# Ultrasound_Test_Prototype.net
KiCad netlist of a schematic drawn in Altium Designer
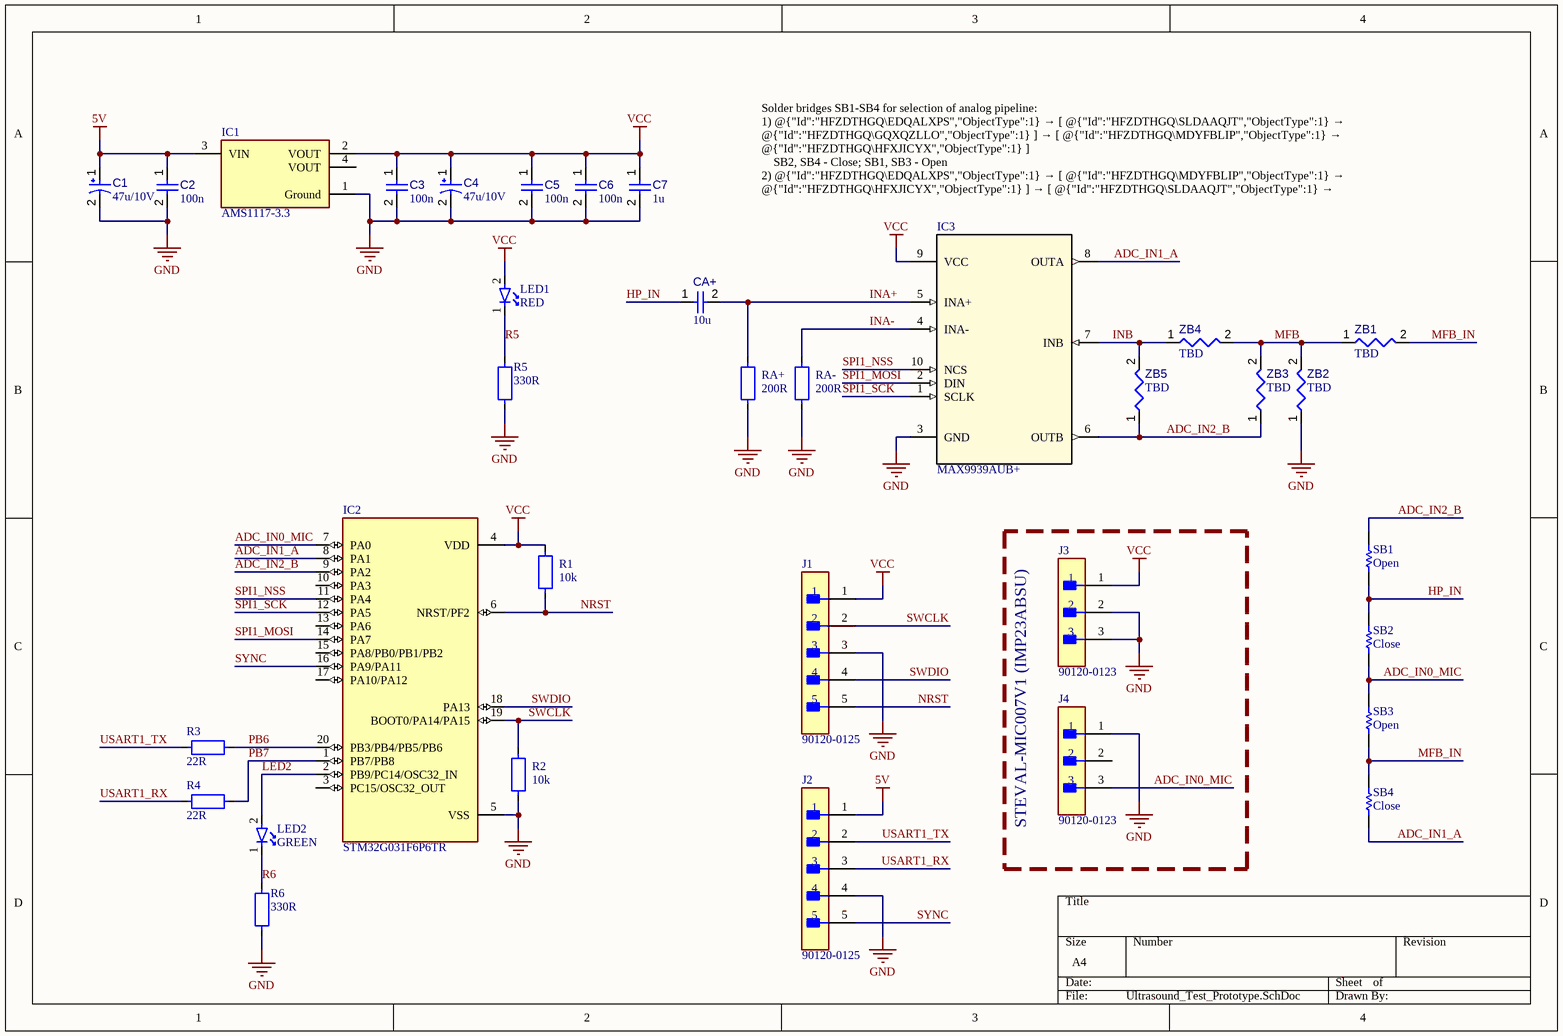
[diagram p0: Ultrasound_Test_Prototype.SchDoc]

(export (version "E")
  (design (tool "Eeschema 10.0.6"))
  (components
    (comp (ref "C1")
      (value "47u/10V")
      (footprint "AVX-TAJ-C-2_L")
      (description "Standard Tantalum, 100 uF, +/- 10%, 10 V, -55 to 125 degC, 2312 (6032 Metric), RoHS, Tape and Reel")
      (fields (field (name "TOLERANCE") "10%") (field (name "MANUFACTURER") "AVX"))
      (libsource (lib "My workspace") (part "CAP-P-2"))
    )
    (comp (ref "C2")
      (value "100n")
      (footprint "CAPC0603(1608)100_L")
      (description "Chip Capacitor, 1µF +/-0.1%, 25V, 0603, Thickness 1 mm")
      (fields (field (name "TOLERANCE") "20%") (field (name "Comment") "Capacitor 1µF +/-0.1% 25V 0603"))
      (libsource (lib "My workspace") (part "CAP-NP-2"))
    )
    (comp (ref "C3")
      (value "100n")
      (footprint "CAPC0603(1608)100_L")
      (description "Chip Capacitor, 1µF +/-0.1%, 25V, 0603, Thickness 1 mm")
      (fields (field (name "TOLERANCE") "20%") (field (name "Comment") "Capacitor 1µF +/-0.1% 25V 0603"))
      (libsource (lib "My workspace") (part "CAP-NP-2"))
    )
    (comp (ref "C4")
      (value "47u/10V")
      (footprint "AVX-TAJ-C-2_L")
      (description "Standard Tantalum, 100 uF, +/- 10%, 10 V, -55 to 125 degC, 2312 (6032 Metric), RoHS, Tape and Reel")
      (fields (field (name "TOLERANCE") "10%") (field (name "MANUFACTURER") "AVX"))
      (libsource (lib "My workspace") (part "CAP-P-2"))
    )
    (comp (ref "C5")
      (value "100n")
      (footprint "CAPC0603(1608)100_L")
      (description "Chip Capacitor, 1µF +/-0.1%, 25V, 0603, Thickness 1 mm")
      (fields (field (name "TOLERANCE") "20%") (field (name "Comment") "Capacitor 1µF +/-0.1% 25V 0603"))
      (libsource (lib "My workspace") (part "CAP-NP-2"))
    )
    (comp (ref "C6")
      (value "100n")
      (footprint "CAPC0603(1608)100_L")
      (description "Chip Capacitor, 1µF +/-0.1%, 25V, 0603, Thickness 1 mm")
      (fields (field (name "TOLERANCE") "20%") (field (name "Comment") "Capacitor 1µF +/-0.1% 25V 0603"))
      (libsource (lib "My workspace") (part "CAP-NP-2"))
    )
    (comp (ref "C7")
      (value "1u")
      (footprint "CAPC0603(1608)100_L")
      (description "Chip Capacitor, 1µF +/-0.1%, 25V, 0603, Thickness 1 mm")
      (fields (field (name "TOLERANCE") "20%") (field (name "Comment") "Capacitor 1µF +/-0.1% 25V 0603"))
      (libsource (lib "My workspace") (part "CAP-NP-2"))
    )
    (comp (ref "CA+")
      (value "10u")
      (footprint "CAPC0603(1608)100_L")
      (description "Chip Capacitor, 1µF +/-0.1%, 25V, 0603, Thickness 1 mm")
      (fields (field (name "TOLERANCE") "20%") (field (name "Comment") "Capacitor 1µF +/-0.1% 25V 0603"))
      (libsource (lib "My workspace") (part "CAP-NP-2"))
    )
    (comp (ref "IC1")
      (value "AMS1117-3.3")
      (footprint "FP-AMS1117-IPC_B")
      (description "Fixed Positive LDO Regulator, 3.3V, 1.3V Dropout, PDSO3")
      (libsource (lib "My workspace") (part "8bdbb5f8e77002000e30dd2845d0354"))
    )
    (comp (ref "IC2")
      (value "STM32G031F6P6TR")
      (footprint "SOIC65P640X120-20N")
      (description "Microcontroller 32-Bit ARM Cortex M0 32KByte Flash 1.7V to 3.6V 20-Pin TSSOP T/R")
      (libsource (lib "My workspace") (part "STM32G031F6P6"))
    )
    (comp (ref "IC3")
      (value "MAX9939AUB+")
      (footprint "21-0061L_MXM-M")
      (description "SPI-Programmable Gain Amplifier (PGA) with Input VOS Trim and Output Op Amp")
      (libsource (lib "My workspace") (part "MAX9939"))
    )
    (comp (ref "J1")
      (value "90120-0125")
      (footprint "FP-90120-0125-MFG")
      (libsource (lib "My workspace") (part "bf93c07fd2649a848d0ec8585582aab"))
    )
    (comp (ref "J2")
      (value "90120-0125")
      (footprint "FP-90120-0125-MFG")
      (libsource (lib "My workspace") (part "bf93c07fd2649a848d0ec8585582aab"))
    )
    (comp (ref "J3")
      (value "90120-0123")
      (footprint "FP-90120-0123-MFG")
      (libsource (lib "My workspace") (part "0d3f023dd272f625e17a2be33dea85f"))
    )
    (comp (ref "J4")
      (value "90120-0123")
      (footprint "FP-90120-0123-MFG")
      (libsource (lib "My workspace") (part "0d3f023dd272f625e17a2be33dea85f"))
    )
    (comp (ref "LED1")
      (value "RED")
      (footprint "FP-SML-21-MFG")
      (description "Single Color LED, Red, Colorless Transparent, 1.4mm")
      (libsource (lib "My workspace") (part "LED"))
    )
    (comp (ref "LED2")
      (value "GREEN")
      (footprint "FP-SML-21-MFG")
      (description "Single Color LED, Red, Colorless Transparent, 1.4mm")
      (libsource (lib "My workspace") (part "LED"))
    )
    (comp (ref "R1")
      (value "10k")
      (footprint "FP-CRCW0603-e3-IPC_C")
      (description "Resistor European Symbol")
      (fields (field (name "Comment") "Resistor European"))
      (libsource (lib "My workspace") (part "R_EU"))
    )
    (comp (ref "R2")
      (value "10k")
      (footprint "FP-CRCW0603-e3-IPC_C")
      (description "Resistor European Symbol")
      (fields (field (name "Comment") "Resistor European"))
      (libsource (lib "My workspace") (part "R_EU"))
    )
    (comp (ref "R3")
      (value "22R")
      (footprint "FP-CRCW0603-e3-IPC_C")
      (description "Resistor European Symbol")
      (fields (field (name "Comment") "Resistor European"))
      (libsource (lib "My workspace") (part "R_EU"))
    )
    (comp (ref "R4")
      (value "22R")
      (footprint "FP-CRCW0603-e3-IPC_C")
      (description "Resistor European Symbol")
      (fields (field (name "Comment") "Resistor European"))
      (libsource (lib "My workspace") (part "R_EU"))
    )
    (comp (ref "R5")
      (value "330R")
      (footprint "FP-CRCW0603-e3-IPC_C")
      (description "Resistor European Symbol")
      (fields (field (name "Comment") "Resistor European"))
      (libsource (lib "My workspace") (part "R_EU"))
    )
    (comp (ref "R6")
      (value "330R")
      (footprint "FP-CRCW0603-e3-IPC_C")
      (description "Resistor European Symbol")
      (fields (field (name "Comment") "Resistor European"))
      (libsource (lib "My workspace") (part "R_EU"))
    )
    (comp (ref "RA+")
      (value "200R")
      (footprint "FP-CRCW0603-e3-IPC_C")
      (description "Resistor European Symbol")
      (fields (field (name "Comment") "Resistor European"))
      (libsource (lib "My workspace") (part "R_EU"))
    )
    (comp (ref "RA-")
      (value "200R")
      (footprint "FP-CRCW0603-e3-IPC_C")
      (description "Resistor European Symbol")
      (fields (field (name "Comment") "Resistor European"))
      (libsource (lib "My workspace") (part "R_EU"))
    )
    (comp (ref "SB1")
      (value "Open")
      (footprint "RESC1005X40X25ML05T05")
      (description "Chip Resistor, 0 Ohm, 0.1 W, -55 to 155 degC, 0402 (1005 Metric)")
      (fields (field (name "TOLERANCE") "5%") (field (name "POWER") "100mW"))
      (libsource (lib "My workspace") (part "RES-2"))
    )
    (comp (ref "SB2")
      (value "Close")
      (footprint "RESC1005X40X25ML05T05")
      (description "Chip Resistor, 0 Ohm, 0.1 W, -55 to 155 degC, 0402 (1005 Metric)")
      (fields (field (name "TOLERANCE") "5%") (field (name "POWER") "100mW"))
      (libsource (lib "My workspace") (part "RES-2"))
    )
    (comp (ref "SB3")
      (value "Open")
      (footprint "RESC1005X40X25ML05T05")
      (description "Chip Resistor, 0 Ohm, 0.1 W, -55 to 155 degC, 0402 (1005 Metric)")
      (fields (field (name "TOLERANCE") "5%") (field (name "POWER") "100mW"))
      (libsource (lib "My workspace") (part "RES-2"))
    )
    (comp (ref "SB4")
      (value "Close")
      (footprint "RESC1005X40X25ML05T05")
      (description "Chip Resistor, 0 Ohm, 0.1 W, -55 to 155 degC, 0402 (1005 Metric)")
      (fields (field (name "TOLERANCE") "5%") (field (name "POWER") "100mW"))
      (libsource (lib "My workspace") (part "RES-2"))
    )
    (comp (ref "ZB1")
      (value "TBD")
      (footprint "RESC1608X55X25ML10T15")
      (description "Chip Resistor, 10 KOhm, +/- 1%, 01 W, -55 to 155 degC, 0603 (1608 Metric)")
      (fields (field (name "POWER") "100mW") (field (name "TOLERANCE") "1%"))
      (libsource (lib "") (part "RES-2_1"))
    )
    (comp (ref "ZB2")
      (value "TBD")
      (footprint "RESC1608X55X25ML10T15")
      (description "Chip Resistor, 10 KOhm, +/- 1%, 01 W, -55 to 155 degC, 0603 (1608 Metric)")
      (fields (field (name "POWER") "100mW") (field (name "TOLERANCE") "1%"))
      (libsource (lib "") (part "RES-2_1"))
    )
    (comp (ref "ZB3")
      (value "TBD")
      (footprint "RESC1608X55X25ML10T15")
      (description "Chip Resistor, 10 KOhm, +/- 1%, 01 W, -55 to 155 degC, 0603 (1608 Metric)")
      (fields (field (name "POWER") "100mW") (field (name "TOLERANCE") "1%"))
      (libsource (lib "") (part "RES-2_1"))
    )
    (comp (ref "ZB4")
      (value "TBD")
      (footprint "RESC1608X55X25ML10T15")
      (description "Chip Resistor, 10 KOhm, +/- 1%, 01 W, -55 to 155 degC, 0603 (1608 Metric)")
      (fields (field (name "POWER") "100mW") (field (name "TOLERANCE") "1%"))
      (libsource (lib "") (part "RES-2_1"))
    )
    (comp (ref "ZB5")
      (value "TBD")
      (footprint "RESC1608X55X25ML10T15")
      (description "Chip Resistor, 10 KOhm, +/- 1%, 01 W, -55 to 155 degC, 0603 (1608 Metric)")
      (fields (field (name "POWER") "100mW") (field (name "TOLERANCE") "1%"))
      (libsource (lib "") (part "RES-2_1"))
    )
  )
  (nets
    (net (code "1") (name "/ADC_IN0_MIC") (class "Default")
      (node (ref "IC2") (pin "7") (pinfunction "PA0_7") (pintype "bidirectional"))
      (node (ref "J4") (pin "3") (pinfunction "3_3") (pintype "passive"))
      (node (ref "SB2") (pin "1") (pinfunction "1_1") (pintype "passive"))
      (node (ref "SB3") (pin "2") (pinfunction "2_2") (pintype "passive"))
    )
    (net (code "2") (name "/ADC_IN1_A") (class "Default")
      (node (ref "IC2") (pin "8") (pinfunction "PA1_8") (pintype "bidirectional"))
      (node (ref "IC3") (pin "8") (pinfunction "OUTA_8") (pintype "output"))
      (node (ref "SB4") (pin "1") (pinfunction "1_1") (pintype "passive"))
    )
    (net (code "3") (name "/ADC_IN2_B") (class "Default")
      (node (ref "IC2") (pin "9") (pinfunction "PA2_9") (pintype "bidirectional"))
      (node (ref "IC3") (pin "6") (pinfunction "OUTB_6") (pintype "output"))
      (node (ref "SB1") (pin "2") (pinfunction "2_2") (pintype "passive"))
      (node (ref "ZB3") (pin "1") (pinfunction "1_1") (pintype "passive"))
      (node (ref "ZB5") (pin "1") (pinfunction "1_1") (pintype "passive"))
    )
    (net (code "4") (name "/HP_IN") (class "Default")
      (node (ref "CA+") (pin "1") (pinfunction "1_1") (pintype "passive"))
      (node (ref "SB1") (pin "1") (pinfunction "1_1") (pintype "passive"))
      (node (ref "SB2") (pin "2") (pinfunction "2_2") (pintype "passive"))
    )
    (net (code "5") (name "/INA+") (class "Default")
      (node (ref "CA+") (pin "2") (pinfunction "2_2") (pintype "passive"))
      (node (ref "IC3") (pin "5") (pinfunction "INA+_5") (pintype "input"))
      (node (ref "RA+") (pin "2") (pinfunction "2_2") (pintype "passive"))
    )
    (net (code "6") (name "/INA-") (class "Default")
      (node (ref "IC3") (pin "4") (pinfunction "INA-_4") (pintype "input"))
      (node (ref "RA-") (pin "2") (pinfunction "2_2") (pintype "passive"))
    )
    (net (code "7") (name "/INB") (class "Default")
      (node (ref "IC3") (pin "7") (pinfunction "INB_7") (pintype "input"))
      (node (ref "ZB4") (pin "1") (pinfunction "1_1") (pintype "passive"))
      (node (ref "ZB5") (pin "2") (pinfunction "2_2") (pintype "passive"))
    )
    (net (code "8") (name "/LED2") (class "Default")
      (node (ref "IC2") (pin "2") (pinfunction "PB9/PC14/OSC32_IN_2") (pintype "bidirectional"))
      (node (ref "LED2") (pin "2") (pinfunction "A_2") (pintype "passive"))
    )
    (net (code "9") (name "/MFB") (class "Default")
      (node (ref "ZB1") (pin "1") (pinfunction "1_1") (pintype "passive"))
      (node (ref "ZB2") (pin "2") (pinfunction "2_2") (pintype "passive"))
      (node (ref "ZB3") (pin "2") (pinfunction "2_2") (pintype "passive"))
      (node (ref "ZB4") (pin "2") (pinfunction "2_2") (pintype "passive"))
    )
    (net (code "10") (name "/MFB_IN") (class "Default")
      (node (ref "SB3") (pin "1") (pinfunction "1_1") (pintype "passive"))
      (node (ref "SB4") (pin "2") (pinfunction "2_2") (pintype "passive"))
      (node (ref "ZB1") (pin "2") (pinfunction "2_2") (pintype "passive"))
    )
    (net (code "11") (name "/NRST") (class "Default")
      (node (ref "IC2") (pin "6") (pinfunction "NRST/PF2_6") (pintype "bidirectional"))
      (node (ref "J1") (pin "5") (pinfunction "5_5") (pintype "passive"))
      (node (ref "R1") (pin "1") (pinfunction "1_1") (pintype "passive"))
    )
    (net (code "12") (name "/PB6") (class "Default")
      (node (ref "IC2") (pin "20") (pinfunction "PB3/PB4/PB5/PB6_20") (pintype "bidirectional"))
      (node (ref "R3") (pin "1") (pinfunction "1_1") (pintype "passive"))
    )
    (net (code "13") (name "/PB7") (class "Default")
      (node (ref "IC2") (pin "1") (pinfunction "PB7/PB8_1") (pintype "bidirectional"))
      (node (ref "R4") (pin "1") (pinfunction "1_1") (pintype "passive"))
    )
    (net (code "14") (name "/R5") (class "Default")
      (node (ref "LED1") (pin "1") (pinfunction "C_1") (pintype "passive"))
      (node (ref "R5") (pin "1") (pinfunction "1_1") (pintype "passive"))
    )
    (net (code "15") (name "/R6") (class "Default")
      (node (ref "LED2") (pin "1") (pinfunction "C_1") (pintype "passive"))
      (node (ref "R6") (pin "1") (pinfunction "1_1") (pintype "passive"))
    )
    (net (code "16") (name "/SPI1_MOSI") (class "Default")
      (node (ref "IC2") (pin "14") (pinfunction "PA7_14") (pintype "bidirectional"))
      (node (ref "IC3") (pin "2") (pinfunction "DIN_2") (pintype "input"))
    )
    (net (code "17") (name "/SPI1_NSS") (class "Default")
      (node (ref "IC2") (pin "11") (pinfunction "PA4_11") (pintype "bidirectional"))
      (node (ref "IC3") (pin "10") (pinfunction "NCS_10") (pintype "input"))
    )
    (net (code "18") (name "/SPI1_SCK") (class "Default")
      (node (ref "IC2") (pin "12") (pinfunction "PA5_12") (pintype "bidirectional"))
      (node (ref "IC3") (pin "1") (pinfunction "SCLK_1") (pintype "input"))
    )
    (net (code "19") (name "/SWCLK") (class "Default")
      (node (ref "IC2") (pin "19") (pinfunction "BOOT0/PA14/PA15_19") (pintype "bidirectional"))
      (node (ref "J1") (pin "2") (pinfunction "2_2") (pintype "passive"))
      (node (ref "R2") (pin "2") (pinfunction "2_2") (pintype "passive"))
    )
    (net (code "20") (name "/SWDIO") (class "Default")
      (node (ref "IC2") (pin "18") (pinfunction "PA13_18") (pintype "bidirectional"))
      (node (ref "J1") (pin "4") (pinfunction "4_4") (pintype "passive"))
    )
    (net (code "21") (name "/SYNC") (class "Default")
      (node (ref "IC2") (pin "16") (pinfunction "PA9/PA11_16") (pintype "bidirectional"))
      (node (ref "J2") (pin "5") (pinfunction "5_5") (pintype "passive"))
    )
    (net (code "22") (name "/USART1_RX") (class "Default")
      (node (ref "J2") (pin "3") (pinfunction "3_3") (pintype "passive"))
      (node (ref "R4") (pin "2") (pinfunction "2_2") (pintype "passive"))
    )
    (net (code "23") (name "/USART1_TX") (class "Default")
      (node (ref "J2") (pin "2") (pinfunction "2_2") (pintype "passive"))
      (node (ref "R3") (pin "2") (pinfunction "2_2") (pintype "passive"))
    )
    (net (code "24") (name "5V") (class "Default")
      (node (ref "C1") (pin "1") (pinfunction "1_1") (pintype "passive"))
      (node (ref "C2") (pin "1") (pinfunction "1_1") (pintype "passive"))
      (node (ref "IC1") (pin "3") (pinfunction "VIN_3") (pintype "power_in"))
      (node (ref "J2") (pin "1") (pinfunction "1_1") (pintype "passive"))
    )
    (net (code "25") (name "GND") (class "Default")
      (node (ref "C1") (pin "2") (pinfunction "2_2") (pintype "passive"))
      (node (ref "C2") (pin "2") (pinfunction "2_2") (pintype "passive"))
      (node (ref "C3") (pin "2") (pinfunction "2_2") (pintype "passive"))
      (node (ref "C4") (pin "2") (pinfunction "2_2") (pintype "passive"))
      (node (ref "C5") (pin "2") (pinfunction "2_2") (pintype "passive"))
      (node (ref "C6") (pin "2") (pinfunction "2_2") (pintype "passive"))
      (node (ref "C7") (pin "2") (pinfunction "2_2") (pintype "passive"))
      (node (ref "IC1") (pin "1") (pinfunction "Ground_1") (pintype "power_in"))
      (node (ref "IC2") (pin "5") (pinfunction "VSS_5") (pintype "power_in"))
      (node (ref "IC3") (pin "3") (pinfunction "GND_3") (pintype "power_in"))
      (node (ref "J1") (pin "3") (pinfunction "3_3") (pintype "passive"))
      (node (ref "J2") (pin "4") (pinfunction "4_4") (pintype "passive"))
      (node (ref "J3") (pin "2") (pinfunction "2_2") (pintype "passive"))
      (node (ref "J3") (pin "3") (pinfunction "3_3") (pintype "passive"))
      (node (ref "J4") (pin "1") (pinfunction "1_1") (pintype "passive"))
      (node (ref "R2") (pin "1") (pinfunction "1_1") (pintype "passive"))
      (node (ref "R5") (pin "2") (pinfunction "2_2") (pintype "passive"))
      (node (ref "R6") (pin "2") (pinfunction "2_2") (pintype "passive"))
      (node (ref "RA+") (pin "1") (pinfunction "1_1") (pintype "passive"))
      (node (ref "RA-") (pin "1") (pinfunction "1_1") (pintype "passive"))
      (node (ref "ZB2") (pin "1") (pinfunction "1_1") (pintype "passive"))
    )
    (net (code "26") (name "VCC") (class "Default")
      (node (ref "C3") (pin "1") (pinfunction "1_1") (pintype "passive"))
      (node (ref "C4") (pin "1") (pinfunction "1_1") (pintype "passive"))
      (node (ref "C5") (pin "1") (pinfunction "1_1") (pintype "passive"))
      (node (ref "C6") (pin "1") (pinfunction "1_1") (pintype "passive"))
      (node (ref "C7") (pin "1") (pinfunction "1_1") (pintype "passive"))
      (node (ref "IC1") (pin "2") (pinfunction "VOUT_2") (pintype "passive"))
      (node (ref "IC2") (pin "4") (pinfunction "VDD_4") (pintype "power_in"))
      (node (ref "IC3") (pin "9") (pinfunction "VCC_9") (pintype "power_in"))
      (node (ref "J1") (pin "1") (pinfunction "1_1") (pintype "passive"))
      (node (ref "J3") (pin "1") (pinfunction "1_1") (pintype "passive"))
      (node (ref "LED1") (pin "2") (pinfunction "A_2") (pintype "passive"))
      (node (ref "R1") (pin "2") (pinfunction "2_2") (pintype "passive"))
    )
    (net (code "27") (name "unconnected-(IC1-VOUT-Pad4)") (class "Default")
      (node (ref "IC1") (pin "4") (pinfunction "VOUT_4") (pintype "passive"))
    )
    (net (code "28") (name "unconnected-(IC2-PA3-Pad10)") (class "Default")
      (node (ref "IC2") (pin "10") (pinfunction "PA3_10") (pintype "bidirectional"))
    )
    (net (code "29") (name "unconnected-(IC2-PA6-Pad13)") (class "Default")
      (node (ref "IC2") (pin "13") (pinfunction "PA6_13") (pintype "bidirectional"))
    )
    (net (code "30") (name "unconnected-(IC2-PA8{slash}PB0{slash}PB1{slash}PB2-Pad15)") (class "Default")
      (node (ref "IC2") (pin "15") (pinfunction "PA8/PB0/PB1/PB2_15") (pintype "bidirectional"))
    )
    (net (code "31") (name "unconnected-(IC2-PA10{slash}PA12-Pad17)") (class "Default")
      (node (ref "IC2") (pin "17") (pinfunction "PA10/PA12_17") (pintype "bidirectional"))
    )
    (net (code "32") (name "unconnected-(IC2-PC15{slash}OSC32_OUT-Pad3)") (class "Default")
      (node (ref "IC2") (pin "3") (pinfunction "PC15/OSC32_OUT_3") (pintype "bidirectional"))
    )
    (net (code "33") (name "unconnected-(J4-Pad2)") (class "Default")
      (node (ref "J4") (pin "2") (pinfunction "2_2") (pintype "passive"))
    )
  )
)
